# mb-001.net
KiCad netlist of a schematic drawn in EAGLE
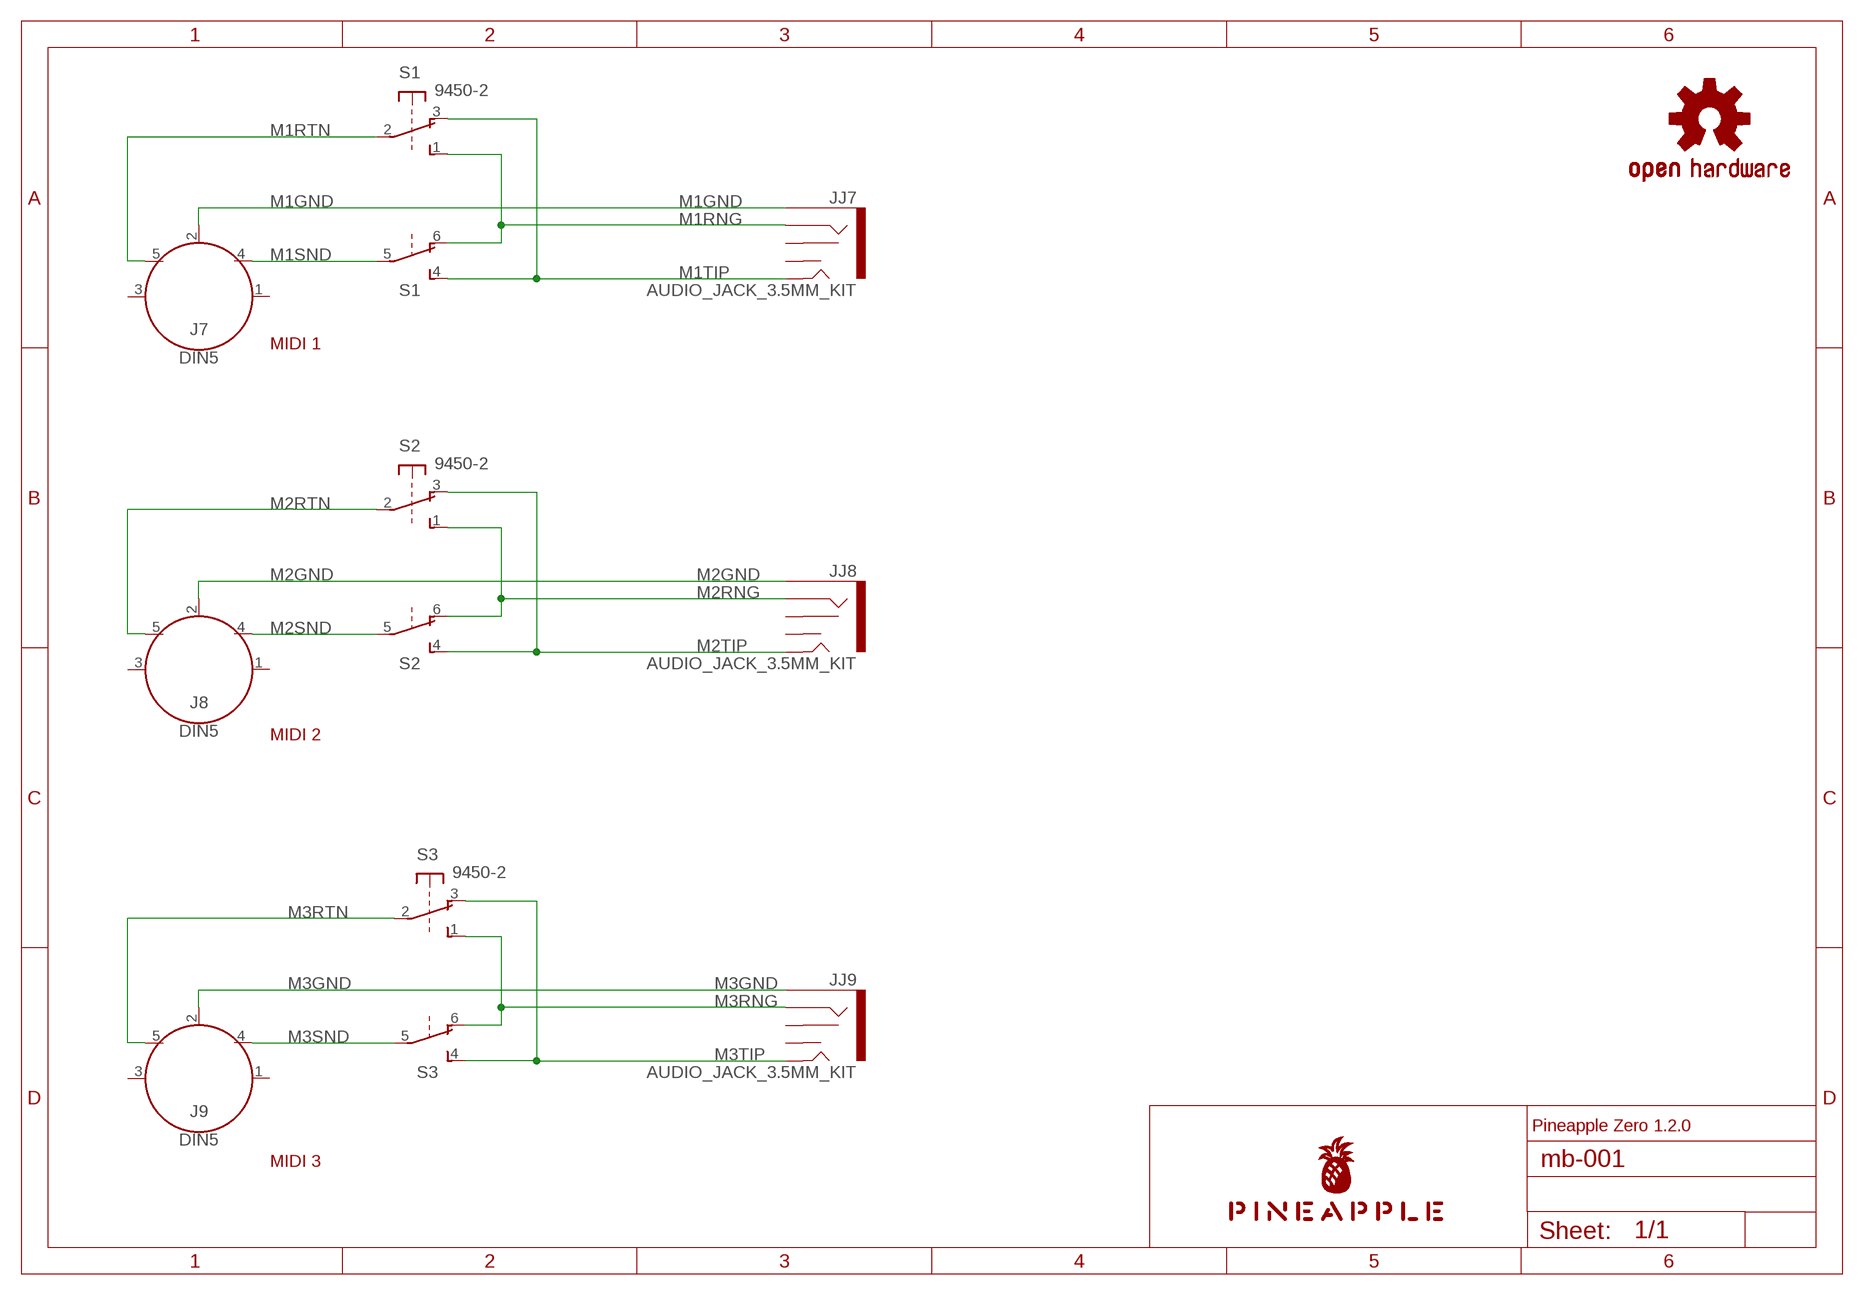
[diagram p0: schematic, sheet 1]

(export (version "E")
  (design (tool "Eeschema 10.0.6"))
  (components
    (comp (ref "J7")
      (value "DIN5")
      (footprint "eagle-import:DIN5-RA-PTH")
      (libsource (lib "eagle-import") (part "DIN5"))
    )
    (comp (ref "J8")
      (value "DIN5")
      (footprint "eagle-import:DIN5-RA-PTH")
      (libsource (lib "eagle-import") (part "DIN5"))
    )
    (comp (ref "J9")
      (value "DIN5")
      (footprint "eagle-import:DIN5-RA-PTH")
      (libsource (lib "eagle-import") (part "DIN5"))
    )
    (comp (ref "JJ7")
      (value "AUDIO_JACK_3.5MM_KIT")
      (footprint "eagle-import:AUDIO-JACK-KIT")
      (libsource (lib "eagle-import") (part "AUDIO_JACK_3.5MM_KIT"))
    )
    (comp (ref "JJ8")
      (value "AUDIO_JACK_3.5MM_KIT")
      (footprint "eagle-import:AUDIO-JACK-KIT")
      (libsource (lib "eagle-import") (part "AUDIO_JACK_3.5MM_KIT"))
    )
    (comp (ref "JJ9")
      (value "AUDIO_JACK_3.5MM_KIT")
      (footprint "eagle-import:AUDIO-JACK-KIT")
      (libsource (lib "eagle-import") (part "AUDIO_JACK_3.5MM_KIT"))
    )
    (comp (ref "LOGO1")
      (value "OSHW-LOGOS-COPPER")
      (footprint "eagle-import:OSHW-LOGO-S_COPPER")
      (libsource (lib "eagle-import") (part "OSHW-LOGOS-COPPER"))
    )
    (comp (ref "S1")
      (value "9450-2")
      (footprint "eagle-import:9450-2")
      (libsource (lib "eagle-import") (part "9450-2"))
    )
    (comp (ref "S2")
      (value "9450-2")
      (footprint "eagle-import:9450-2")
      (libsource (lib "eagle-import") (part "9450-2"))
    )
    (comp (ref "S3")
      (value "9450-2")
      (footprint "eagle-import:9450-2")
      (libsource (lib "eagle-import") (part "9450-2"))
    )
    (comp (ref "U$1")
      (value "PINEAPPLE450")
      (footprint "eagle-import:PINEAPPLE450")
      (libsource (lib "eagle-import") (part "PINEAPPLE450"))
    )
  )
  (nets
    (net (code "1") (name "/M1GND") (class "Default")
      (node (ref "J7") (pin "2") (pinfunction "2_2") (pintype "bidirectional"))
      (node (ref "JJ7") (pin "SLEEVE") (pinfunction "SLEEVE_SLEEVE") (pintype "bidirectional"))
    )
    (net (code "2") (name "/M1RNG") (class "Default")
      (node (ref "JJ7") (pin "RING") (pinfunction "RING_RING") (pintype "bidirectional"))
      (node (ref "S1") (pin "1") (pinfunction "S_1") (pintype "passive"))
      (node (ref "S1") (pin "6") (pinfunction "O_6") (pintype "passive"))
    )
    (net (code "3") (name "/M1RTN") (class "Default")
      (node (ref "J7") (pin "5") (pinfunction "5_5") (pintype "bidirectional"))
      (node (ref "S1") (pin "2") (pinfunction "P_2") (pintype "passive"))
    )
    (net (code "4") (name "/M1SND") (class "Default")
      (node (ref "J7") (pin "4") (pinfunction "4_4") (pintype "bidirectional"))
      (node (ref "S1") (pin "5") (pinfunction "P_5") (pintype "passive"))
    )
    (net (code "5") (name "/M1TIP") (class "Default")
      (node (ref "JJ7") (pin "TIP") (pinfunction "TIP_TIP") (pintype "bidirectional"))
      (node (ref "S1") (pin "3") (pinfunction "O_3") (pintype "passive"))
      (node (ref "S1") (pin "4") (pinfunction "S_4") (pintype "passive"))
    )
    (net (code "6") (name "/M2GND") (class "Default")
      (node (ref "J8") (pin "2") (pinfunction "2_2") (pintype "bidirectional"))
      (node (ref "JJ8") (pin "SLEEVE") (pinfunction "SLEEVE_SLEEVE") (pintype "bidirectional"))
    )
    (net (code "7") (name "/M2RNG") (class "Default")
      (node (ref "JJ8") (pin "RING") (pinfunction "RING_RING") (pintype "bidirectional"))
      (node (ref "S2") (pin "1") (pinfunction "S_1") (pintype "passive"))
      (node (ref "S2") (pin "6") (pinfunction "O_6") (pintype "passive"))
    )
    (net (code "8") (name "/M2RTN") (class "Default")
      (node (ref "J8") (pin "5") (pinfunction "5_5") (pintype "bidirectional"))
      (node (ref "S2") (pin "2") (pinfunction "P_2") (pintype "passive"))
    )
    (net (code "9") (name "/M2SND") (class "Default")
      (node (ref "J8") (pin "4") (pinfunction "4_4") (pintype "bidirectional"))
      (node (ref "S2") (pin "5") (pinfunction "P_5") (pintype "passive"))
    )
    (net (code "10") (name "/M2TIP") (class "Default")
      (node (ref "JJ8") (pin "TIP") (pinfunction "TIP_TIP") (pintype "bidirectional"))
      (node (ref "S2") (pin "3") (pinfunction "O_3") (pintype "passive"))
      (node (ref "S2") (pin "4") (pinfunction "S_4") (pintype "passive"))
    )
    (net (code "11") (name "/M3GND") (class "Default")
      (node (ref "J9") (pin "2") (pinfunction "2_2") (pintype "bidirectional"))
      (node (ref "JJ9") (pin "SLEEVE") (pinfunction "SLEEVE_SLEEVE") (pintype "bidirectional"))
    )
    (net (code "12") (name "/M3RNG") (class "Default")
      (node (ref "JJ9") (pin "RING") (pinfunction "RING_RING") (pintype "bidirectional"))
      (node (ref "S3") (pin "1") (pinfunction "S_1") (pintype "passive"))
      (node (ref "S3") (pin "6") (pinfunction "O_6") (pintype "passive"))
    )
    (net (code "13") (name "/M3RTN") (class "Default")
      (node (ref "J9") (pin "5") (pinfunction "5_5") (pintype "bidirectional"))
      (node (ref "S3") (pin "2") (pinfunction "P_2") (pintype "passive"))
    )
    (net (code "14") (name "/M3SND") (class "Default")
      (node (ref "J9") (pin "4") (pinfunction "4_4") (pintype "bidirectional"))
      (node (ref "S3") (pin "5") (pinfunction "P_5") (pintype "passive"))
    )
    (net (code "15") (name "/M3TIP") (class "Default")
      (node (ref "JJ9") (pin "TIP") (pinfunction "TIP_TIP") (pintype "bidirectional"))
      (node (ref "S3") (pin "3") (pinfunction "O_3") (pintype "passive"))
      (node (ref "S3") (pin "4") (pinfunction "S_4") (pintype "passive"))
    )
    (net (code "16") (name "unconnected-(J7-Pad1)") (class "Default")
      (node (ref "J7") (pin "1") (pinfunction "1_1") (pintype "bidirectional"))
    )
    (net (code "17") (name "unconnected-(J7-Pad3)") (class "Default")
      (node (ref "J7") (pin "3") (pinfunction "3_3") (pintype "bidirectional"))
    )
    (net (code "18") (name "unconnected-(J8-Pad1)") (class "Default")
      (node (ref "J8") (pin "1") (pinfunction "1_1") (pintype "bidirectional"))
    )
    (net (code "19") (name "unconnected-(J8-Pad3)") (class "Default")
      (node (ref "J8") (pin "3") (pinfunction "3_3") (pintype "bidirectional"))
    )
    (net (code "20") (name "unconnected-(J9-Pad1)") (class "Default")
      (node (ref "J9") (pin "1") (pinfunction "1_1") (pintype "bidirectional"))
    )
    (net (code "21") (name "unconnected-(J9-Pad3)") (class "Default")
      (node (ref "J9") (pin "3") (pinfunction "3_3") (pintype "bidirectional"))
    )
    (net (code "22") (name "unconnected-(JJ7-PadRSH)") (class "Default")
      (node (ref "JJ7") (pin "RSH") (pinfunction "RSH_RSH") (pintype "bidirectional"))
    )
    (net (code "23") (name "unconnected-(JJ7-PadTSH)") (class "Default")
      (node (ref "JJ7") (pin "TSH") (pinfunction "TSH_TSH") (pintype "bidirectional"))
    )
    (net (code "24") (name "unconnected-(JJ8-PadRSH)") (class "Default")
      (node (ref "JJ8") (pin "RSH") (pinfunction "RSH_RSH") (pintype "bidirectional"))
    )
    (net (code "25") (name "unconnected-(JJ8-PadTSH)") (class "Default")
      (node (ref "JJ8") (pin "TSH") (pinfunction "TSH_TSH") (pintype "bidirectional"))
    )
    (net (code "26") (name "unconnected-(JJ9-PadRSH)") (class "Default")
      (node (ref "JJ9") (pin "RSH") (pinfunction "RSH_RSH") (pintype "bidirectional"))
    )
    (net (code "27") (name "unconnected-(JJ9-PadTSH)") (class "Default")
      (node (ref "JJ9") (pin "TSH") (pinfunction "TSH_TSH") (pintype "bidirectional"))
    )
  )
)
